# optoacopulador.net
KiCad netlist of a schematic drawn in EasyEDA Pro
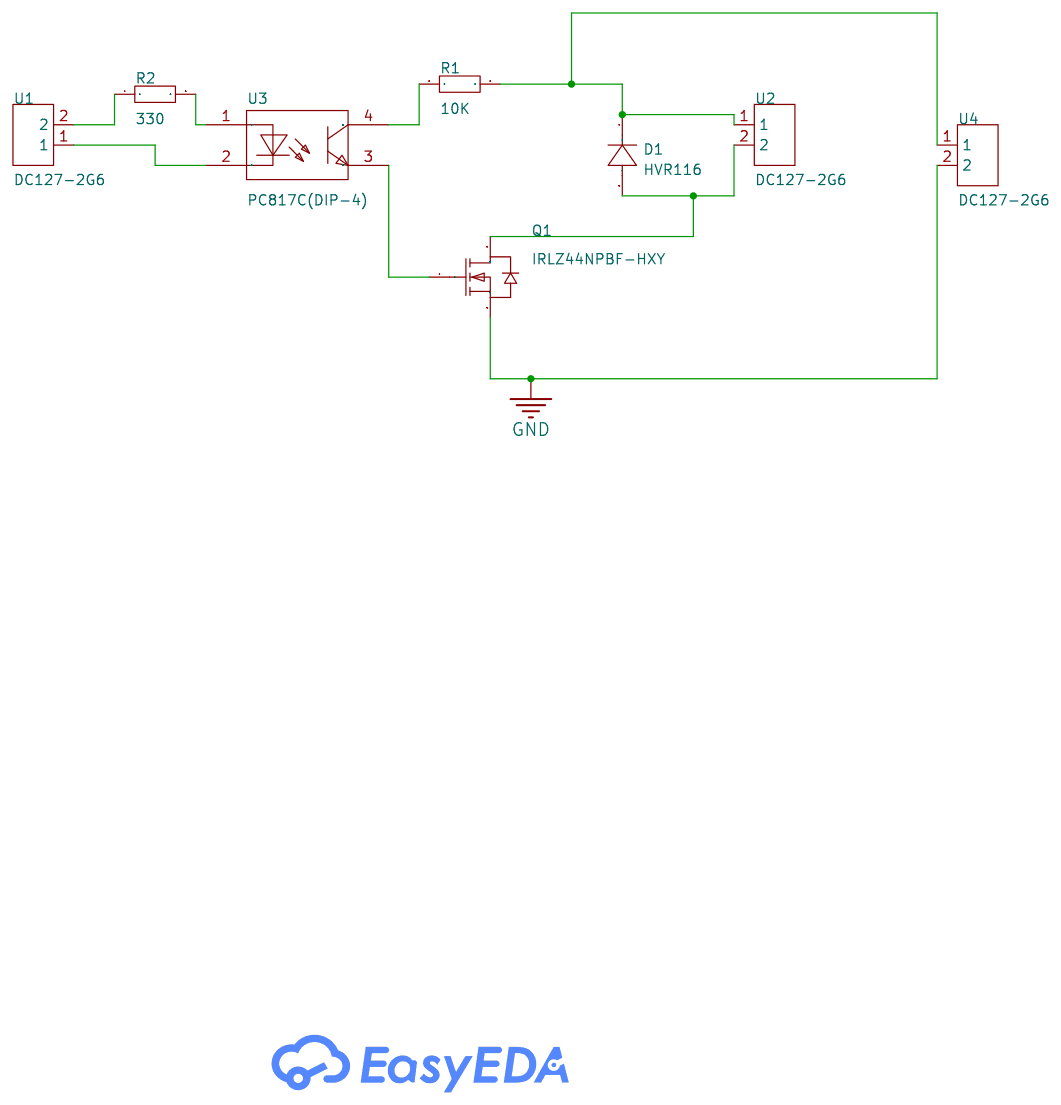
[diagram p0: schematic sheet]

(export (version "E")
  (design (tool "Eeschema 10.0.6"))
  (components
    (comp (ref "D1")
      (value "HVR116")
      (footprint "easyedapro:DO-41_BD2.4-L4.7-P8.70-D0.8-RD")
      (fields (field (name "Manufacturer") "EIC"))
      (libsource (lib "easyedapro") (part "HVR116"))
    )
    (comp (ref "Q1")
      (value "IRLZ44NPBF-HXY")
      (footprint "easyedapro:TO-220-3_L9.9-W4.5-P2.54-L-1")
      (fields (field (name "Manufacturer") "HXY MOSFET(华轩阳电子)"))
      (libsource (lib "easyedapro") (part "IRLZ44NPBF-HXY"))
    )
    (comp (ref "R1") (value "10K") (footprint "easyedapro:R0603") (libsource (lib "easyedapro") (part "Res")))
    (comp (ref "R2") (value "330") (footprint "easyedapro:R0603") (libsource (lib "easyedapro") (part "Res")))
    (comp (ref "U1")
      (value "DC127-2G6")
      (footprint "easyedapro:CONN-TH_DC127-2G6")
      (fields (field (name "Manufacturer") "CONNFLY"))
      (libsource (lib "easyedapro") (part "DC127-2G6"))
    )
    (comp (ref "U2")
      (value "DC127-2G6")
      (footprint "easyedapro:CONN-TH_DC127-2G6")
      (fields (field (name "Manufacturer") "CONNFLY"))
      (libsource (lib "easyedapro") (part "DC127-2G6"))
    )
    (comp (ref "U3")
      (value "PC817C(DIP-4)")
      (footprint "easyedapro:DIP-4_L4.6-W6.5-P2.54-LS7.6-BL")
      (fields (field (name "Manufacturer") "SEP(威旺)"))
      (libsource (lib "easyedapro") (part "PC817C(DIP-4)"))
    )
    (comp (ref "U4")
      (value "DC127-2G6")
      (footprint "easyedapro:CONN-TH_DC127-2G6")
      (fields (field (name "Manufacturer") "CONNFLY"))
      (libsource (lib "easyedapro") (part "DC127-2G6"))
    )
  )
  (nets
    (net (code "1") (name "GND") (class "Default")
      (node (ref "Q1") (pin "3") (pinfunction "S_3") (pintype "unspecified"))
      (node (ref "U4") (pin "2") (pinfunction "2_2") (pintype "unspecified"))
    )
    (net (code "2") (name "Net-(D1-A)") (class "Default")
      (node (ref "D1") (pin "2") (pinfunction "A_2") (pintype "unspecified"))
      (node (ref "Q1") (pin "2") (pinfunction "D_2") (pintype "unspecified"))
      (node (ref "U2") (pin "2") (pinfunction "2_2") (pintype "unspecified"))
    )
    (net (code "3") (name "Net-(D1-K)") (class "Default")
      (node (ref "D1") (pin "1") (pinfunction "K_1") (pintype "unspecified"))
      (node (ref "R1") (pin "1") (pinfunction "1_1") (pintype "input"))
      (node (ref "U2") (pin "1") (pinfunction "1_1") (pintype "unspecified"))
      (node (ref "U4") (pin "1") (pinfunction "1_1") (pintype "unspecified"))
    )
    (net (code "4") (name "Net-(Q1-G)") (class "Default")
      (node (ref "Q1") (pin "1") (pinfunction "G_1") (pintype "unspecified"))
      (node (ref "U3") (pin "3") (pinfunction "EM_3") (pintype "unspecified"))
    )
    (net (code "5") (name "Net-(R2-Pad1)") (class "Default")
      (node (ref "R2") (pin "1") (pinfunction "1_1") (pintype "input"))
      (node (ref "U1") (pin "2") (pinfunction "2_2") (pintype "unspecified"))
    )
    (net (code "6") (name "Net-(U3-AN)") (class "Default")
      (node (ref "R2") (pin "2") (pinfunction "2_2") (pintype "input"))
      (node (ref "U3") (pin "1") (pinfunction "AN_1") (pintype "unspecified"))
    )
    (net (code "7") (name "Net-(U3-CAT)") (class "Default")
      (node (ref "U1") (pin "1") (pinfunction "1_1") (pintype "unspecified"))
      (node (ref "U3") (pin "2") (pinfunction "CAT_2") (pintype "unspecified"))
    )
    (net (code "8") (name "Net-(U3-COL)") (class "Default")
      (node (ref "R1") (pin "2") (pinfunction "2_2") (pintype "input"))
      (node (ref "U3") (pin "4") (pinfunction "COL_4") (pintype "unspecified"))
    )
  )
)
